# PLEN2_EdisonBoard.net
KiCad netlist of a schematic drawn in EAGLE
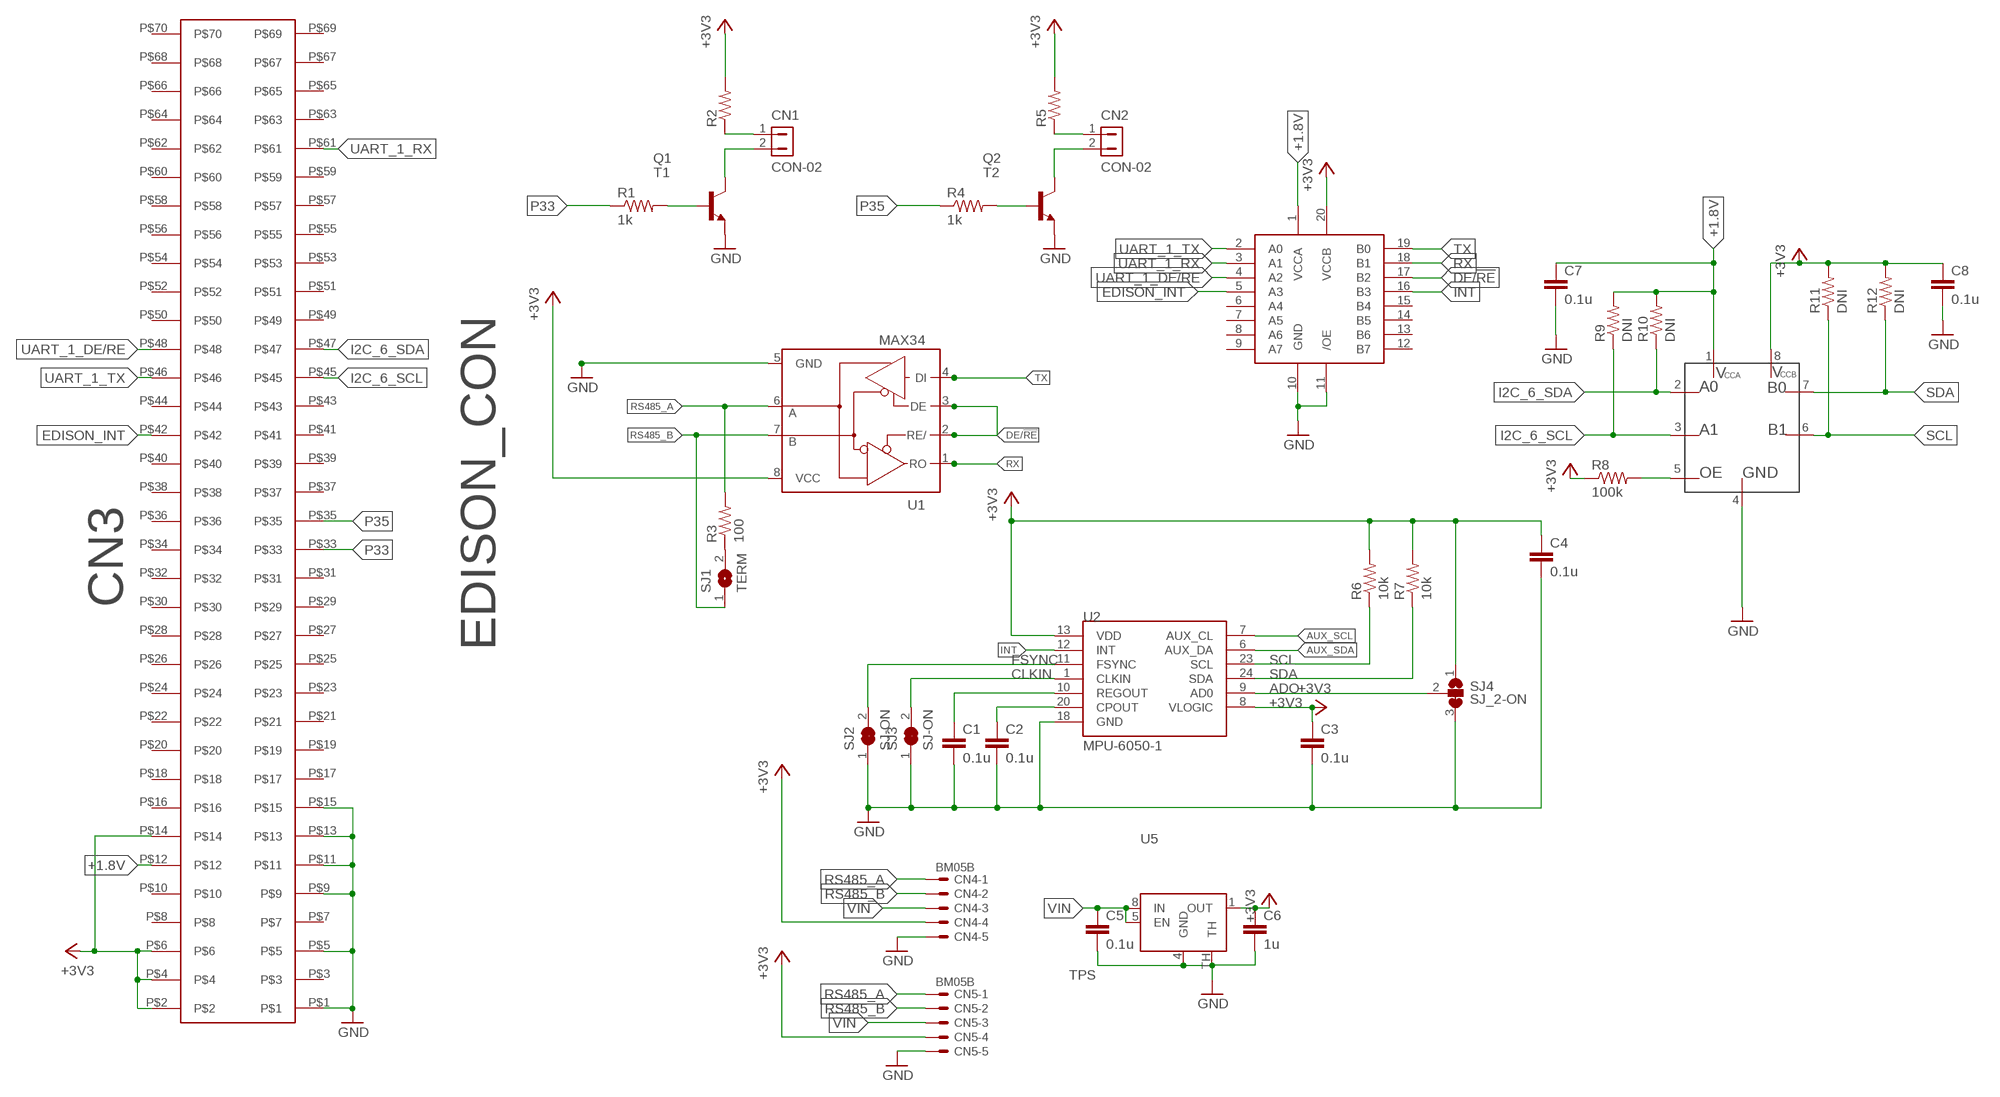
[diagram p0: schematic, sheet 1]

(export (version "E")
  (design (tool "Eeschema 10.0.6"))
  (components
    (comp (ref "C1")
      (value "0.1u")
      (footprint "eagle-import:C0603")
      (libsource (lib "eagle-import") (part "C-EUC0603"))
    )
    (comp (ref "C2")
      (value "0.1u")
      (footprint "eagle-import:C0603")
      (libsource (lib "eagle-import") (part "C-EUC0603"))
    )
    (comp (ref "C3")
      (value "0.1u")
      (footprint "eagle-import:C0603")
      (libsource (lib "eagle-import") (part "C-EUC0603"))
    )
    (comp (ref "C4")
      (value "0.1u")
      (footprint "eagle-import:C0603")
      (libsource (lib "eagle-import") (part "C-EUC0603"))
    )
    (comp (ref "C5")
      (value "0.1u")
      (footprint "eagle-import:C0603")
      (libsource (lib "eagle-import") (part "C-EUC0603"))
    )
    (comp (ref "C6")
      (value "1u")
      (footprint "eagle-import:C0603")
      (libsource (lib "eagle-import") (part "C-EUC0603"))
    )
    (comp (ref "C7")
      (value "0.1u")
      (footprint "eagle-import:C0603")
      (libsource (lib "eagle-import") (part "C-EUC0603"))
    )
    (comp (ref "C8")
      (value "0.1u")
      (footprint "eagle-import:C0603")
      (libsource (lib "eagle-import") (part "C-EUC0603"))
    )
    (comp (ref "CN1")
      (value "CON-02")
      (footprint "eagle-import:SIP-100-02")
      (libsource (lib "eagle-import") (part "CON-02"))
    )
    (comp (ref "CN2")
      (value "CON-02")
      (footprint "eagle-import:SIP-100-02")
      (libsource (lib "eagle-import") (part "CON-02"))
    )
    (comp (ref "CN3")
      (value "EDISON_CON")
      (footprint "eagle-import:EDISON_CON")
      (libsource (lib "eagle-import") (part "EDISON_CON"))
    )
    (comp (ref "CN4")
      (value "BM05B")
      (footprint "eagle-import:BM05B-SRSS-TB")
      (libsource (lib "eagle-import") (part "?M05B-SRSS-TBB"))
    )
    (comp (ref "CN5")
      (value "BM05B")
      (footprint "eagle-import:BM05B-SRSS-TB")
      (libsource (lib "eagle-import") (part "?M05B-SRSS-TBB"))
    )
    (comp (ref "Q1")
      (value "T1")
      (footprint "eagle-import:SOT23-BEC")
      (libsource (lib "eagle-import") (part "BC817SMD-40LT1"))
    )
    (comp (ref "Q2")
      (value "T2")
      (footprint "eagle-import:SOT23-BEC")
      (libsource (lib "eagle-import") (part "BC817SMD-40LT1"))
    )
    (comp (ref "R1")
      (value "1k")
      (footprint "eagle-import:R0603")
      (libsource (lib "eagle-import") (part "R-US_R0603"))
    )
    (comp (ref "R2")
      (value "R-US_R0603")
      (footprint "eagle-import:R0603")
      (libsource (lib "eagle-import") (part "R-US_R0603"))
    )
    (comp (ref "R3")
      (value "100")
      (footprint "eagle-import:R0603")
      (libsource (lib "eagle-import") (part "R-US_R0603"))
    )
    (comp (ref "R4")
      (value "1k")
      (footprint "eagle-import:R0603")
      (libsource (lib "eagle-import") (part "R-US_R0603"))
    )
    (comp (ref "R5")
      (value "R-US_R0603")
      (footprint "eagle-import:R0603")
      (libsource (lib "eagle-import") (part "R-US_R0603"))
    )
    (comp (ref "R6")
      (value "10k")
      (footprint "eagle-import:R0603")
      (libsource (lib "eagle-import") (part "R-US_R0603"))
    )
    (comp (ref "R7")
      (value "10k")
      (footprint "eagle-import:R0603")
      (libsource (lib "eagle-import") (part "R-US_R0603"))
    )
    (comp (ref "R8")
      (value "100k")
      (footprint "eagle-import:R0603")
      (libsource (lib "eagle-import") (part "R-US_R0603"))
    )
    (comp (ref "R9")
      (value "DNI")
      (footprint "eagle-import:R0603")
      (libsource (lib "eagle-import") (part "R-US_R0603"))
    )
    (comp (ref "R10")
      (value "DNI")
      (footprint "eagle-import:R0603")
      (libsource (lib "eagle-import") (part "R-US_R0603"))
    )
    (comp (ref "R11")
      (value "DNI")
      (footprint "eagle-import:R0603")
      (libsource (lib "eagle-import") (part "R-US_R0603"))
    )
    (comp (ref "R12")
      (value "DNI")
      (footprint "eagle-import:R0603")
      (libsource (lib "eagle-import") (part "R-US_R0603"))
    )
    (comp (ref "SJ1")
      (value "TERM")
      (footprint "eagle-import:SJ")
      (libsource (lib "eagle-import") (part "SJ"))
    )
    (comp (ref "SJ2")
      (value "SJ-ON")
      (footprint "eagle-import:SJ-ON")
      (libsource (lib "eagle-import") (part "SJ-ON"))
    )
    (comp (ref "SJ3")
      (value "SJ-ON")
      (footprint "eagle-import:SJ-ON")
      (libsource (lib "eagle-import") (part "SJ-ON"))
    )
    (comp (ref "SJ4")
      (value "SJ_2-ON")
      (footprint "eagle-import:SJ_2-ON")
      (libsource (lib "eagle-import") (part "SJ_2-ON"))
    )
    (comp (ref "U$2")
      (value "FXMA2102_MAC08A")
      (footprint "eagle-import:FXMA2102_MAC08A")
      (libsource (lib "eagle-import") (part "FXMA2102_MAC08A"))
    )
    (comp (ref "U1")
      (value "MAX34")
      (footprint "eagle-import:SO08SHORT")
      (libsource (lib "eagle-import") (part "MAX34SHORT"))
    )
    (comp (ref "U2")
      (value "MPU-6050-1")
      (footprint "eagle-import:QFN-24-4MM2")
      (libsource (lib "eagle-import") (part "MPU-6050-1"))
    )
    (comp (ref "U3")
      (value "FXMA108FXMA108")
      (footprint "eagle-import:FXMA108")
      (libsource (lib "eagle-import") (part "FXMA108FXMA108"))
    )
    (comp (ref "U5")
      (value "TPS")
      (footprint "eagle-import:S-PVSON-N8")
      (libsource (lib "eagle-import") (part "TPS73733"))
    )
  )
  (nets
    (net (code "1") (name "+1.8V") (class "Default")
      (node (ref "C7") (pin "1") (pinfunction "1_1") (pintype "passive"))
      (node (ref "CN3") (pin "P$12") (pinfunction "P$12_P$12") (pintype "bidirectional"))
      (node (ref "R10") (pin "2") (pinfunction "2_2") (pintype "passive"))
      (node (ref "R9") (pin "2") (pinfunction "2_2") (pintype "passive"))
      (node (ref "U$2") (pin "PIN1") (pinfunction "P1_PIN1") (pintype "bidirectional"))
      (node (ref "U3") (pin "1") (pinfunction "VCCA_1") (pintype "bidirectional"))
    )
    (net (code "2") (name "+3V3") (class "Default")
      (node (ref "C3") (pin "1") (pinfunction "1_1") (pintype "passive"))
      (node (ref "C4") (pin "1") (pinfunction "1_1") (pintype "passive"))
      (node (ref "C6") (pin "1") (pinfunction "1_1") (pintype "passive"))
      (node (ref "C8") (pin "1") (pinfunction "1_1") (pintype "passive"))
      (node (ref "CN3") (pin "P$14") (pinfunction "P$14_P$14") (pintype "bidirectional"))
      (node (ref "CN3") (pin "P$2") (pinfunction "P$2_P$2") (pintype "bidirectional"))
      (node (ref "CN3") (pin "P$4") (pinfunction "P$4_P$4") (pintype "bidirectional"))
      (node (ref "CN3") (pin "P$6") (pinfunction "P$6_P$6") (pintype "bidirectional"))
      (node (ref "CN4") (pin "4") (pinfunction "S_4") (pintype "passive"))
      (node (ref "CN5") (pin "4") (pinfunction "S_4") (pintype "passive"))
      (node (ref "R11") (pin "2") (pinfunction "2_2") (pintype "passive"))
      (node (ref "R12") (pin "2") (pinfunction "2_2") (pintype "passive"))
      (node (ref "R2") (pin "2") (pinfunction "2_2") (pintype "passive"))
      (node (ref "R5") (pin "2") (pinfunction "2_2") (pintype "passive"))
      (node (ref "R6") (pin "2") (pinfunction "2_2") (pintype "passive"))
      (node (ref "R7") (pin "2") (pinfunction "2_2") (pintype "passive"))
      (node (ref "R8") (pin "1") (pinfunction "1_1") (pintype "passive"))
      (node (ref "SJ4") (pin "1") (pinfunction "1_1") (pintype "passive"))
      (node (ref "U$2") (pin "PIN8") (pinfunction "P8_PIN8") (pintype "bidirectional"))
      (node (ref "U1") (pin "8") (pinfunction "VCC_8") (pintype "power_in"))
      (node (ref "U2") (pin "13") (pinfunction "VDD_13") (pintype "bidirectional"))
      (node (ref "U2") (pin "8") (pinfunction "VLOGIC_8") (pintype "bidirectional"))
      (node (ref "U3") (pin "20") (pinfunction "VCCB_20") (pintype "bidirectional"))
      (node (ref "U5") (pin "1") (pinfunction "OUT_1") (pintype "passive"))
    )
    (net (code "3") (name "/ADO") (class "Default")
      (node (ref "SJ4") (pin "2") (pinfunction "2_2") (pintype "passive"))
      (node (ref "U2") (pin "9") (pinfunction "AD0_9") (pintype "bidirectional"))
    )
    (net (code "4") (name "/CLKIN") (class "Default")
      (node (ref "SJ3") (pin "2") (pinfunction "2_2") (pintype "passive"))
      (node (ref "U2") (pin "1") (pinfunction "CLKIN_1") (pintype "bidirectional"))
    )
    (net (code "5") (name "/DE{slash}~{RE}") (class "Default")
      (node (ref "U1") (pin "2") (pinfunction "RE/_2") (pintype "input"))
      (node (ref "U1") (pin "3") (pinfunction "DE_3") (pintype "input"))
      (node (ref "U3") (pin "17") (pinfunction "B2_17") (pintype "bidirectional"))
    )
    (net (code "6") (name "/FSYNC") (class "Default")
      (node (ref "SJ2") (pin "2") (pinfunction "2_2") (pintype "passive"))
      (node (ref "U2") (pin "11") (pinfunction "FSYNC_11") (pintype "bidirectional"))
    )
    (net (code "7") (name "AUX_SCL") (class "Default")
      (node (ref "U2") (pin "7") (pinfunction "AUX_CL_7") (pintype "bidirectional"))
    )
    (net (code "8") (name "AUX_SDA") (class "Default")
      (node (ref "U2") (pin "6") (pinfunction "AUX_DA_6") (pintype "bidirectional"))
    )
    (net (code "9") (name "EDISON_INT") (class "Default")
      (node (ref "CN3") (pin "P$42") (pinfunction "P$42_P$42") (pintype "bidirectional"))
      (node (ref "U3") (pin "5") (pinfunction "A3_5") (pintype "bidirectional"))
    )
    (net (code "10") (name "GND") (class "Default")
      (node (ref "C1") (pin "2") (pinfunction "2_2") (pintype "passive"))
      (node (ref "C2") (pin "2") (pinfunction "2_2") (pintype "passive"))
      (node (ref "C3") (pin "2") (pinfunction "2_2") (pintype "passive"))
      (node (ref "C4") (pin "2") (pinfunction "2_2") (pintype "passive"))
      (node (ref "C5") (pin "2") (pinfunction "2_2") (pintype "passive"))
      (node (ref "C6") (pin "2") (pinfunction "2_2") (pintype "passive"))
      (node (ref "C7") (pin "2") (pinfunction "2_2") (pintype "passive"))
      (node (ref "C8") (pin "2") (pinfunction "2_2") (pintype "passive"))
      (node (ref "CN3") (pin "P$1") (pinfunction "P$1_P$1") (pintype "bidirectional"))
      (node (ref "CN3") (pin "P$11") (pinfunction "P$11_P$11") (pintype "bidirectional"))
      (node (ref "CN3") (pin "P$13") (pinfunction "P$13_P$13") (pintype "bidirectional"))
      (node (ref "CN3") (pin "P$15") (pinfunction "P$15_P$15") (pintype "bidirectional"))
      (node (ref "CN3") (pin "P$5") (pinfunction "P$5_P$5") (pintype "bidirectional"))
      (node (ref "CN3") (pin "P$9") (pinfunction "P$9_P$9") (pintype "bidirectional"))
      (node (ref "CN4") (pin "5") (pinfunction "S_5") (pintype "passive"))
      (node (ref "CN5") (pin "5") (pinfunction "S_5") (pintype "passive"))
      (node (ref "Q1") (pin "E") (pinfunction "E_E") (pintype "passive"))
      (node (ref "Q2") (pin "E") (pinfunction "E_E") (pintype "passive"))
      (node (ref "SJ2") (pin "1") (pinfunction "1_1") (pintype "passive"))
      (node (ref "SJ3") (pin "1") (pinfunction "1_1") (pintype "passive"))
      (node (ref "SJ4") (pin "3") (pinfunction "3_3") (pintype "passive"))
      (node (ref "U$2") (pin "PIN4") (pinfunction "P4_PIN4") (pintype "bidirectional"))
      (node (ref "U1") (pin "5") (pinfunction "GND_5") (pintype "power_in"))
      (node (ref "U2") (pin "18") (pinfunction "GND_18") (pintype "bidirectional"))
      (node (ref "U3") (pin "10") (pinfunction "GND_10") (pintype "bidirectional"))
      (node (ref "U3") (pin "11") (pinfunction "/OE_11") (pintype "bidirectional"))
      (node (ref "U5") (pin "4") (pinfunction "GND_4") (pintype "power_in"))
      (node (ref "U5") (pin "TH") (pinfunction "TH_TH") (pintype "power_in"))
    )
    (net (code "11") (name "I2C_6_SCL") (class "Default")
      (node (ref "CN3") (pin "P$45") (pinfunction "P$45_P$45") (pintype "bidirectional"))
      (node (ref "R9") (pin "1") (pinfunction "1_1") (pintype "passive"))
      (node (ref "U$2") (pin "PIN3") (pinfunction "P3_PIN3") (pintype "bidirectional"))
    )
    (net (code "12") (name "I2C_6_SDA") (class "Default")
      (node (ref "CN3") (pin "P$47") (pinfunction "P$47_P$47") (pintype "bidirectional"))
      (node (ref "R10") (pin "1") (pinfunction "1_1") (pintype "passive"))
      (node (ref "U$2") (pin "PIN2") (pinfunction "P2_PIN2") (pintype "bidirectional"))
    )
    (net (code "13") (name "INT") (class "Default")
      (node (ref "U2") (pin "12") (pinfunction "INT_12") (pintype "bidirectional"))
      (node (ref "U3") (pin "16") (pinfunction "B3_16") (pintype "bidirectional"))
    )
    (net (code "14") (name "Net-(CN1-Pad1)") (class "Default")
      (node (ref "CN1") (pin "1") (pinfunction "1_1") (pintype "passive"))
      (node (ref "R2") (pin "1") (pinfunction "1_1") (pintype "passive"))
    )
    (net (code "15") (name "Net-(CN1-Pad2)") (class "Default")
      (node (ref "CN1") (pin "2") (pinfunction "2_2") (pintype "passive"))
      (node (ref "Q1") (pin "C") (pinfunction "C_C") (pintype "passive"))
    )
    (net (code "16") (name "Net-(CN2-Pad1)") (class "Default")
      (node (ref "CN2") (pin "1") (pinfunction "1_1") (pintype "passive"))
      (node (ref "R5") (pin "1") (pinfunction "1_1") (pintype "passive"))
    )
    (net (code "17") (name "Net-(CN2-Pad2)") (class "Default")
      (node (ref "CN2") (pin "2") (pinfunction "2_2") (pintype "passive"))
      (node (ref "Q2") (pin "C") (pinfunction "C_C") (pintype "passive"))
    )
    (net (code "18") (name "Net-(Q1-PadB)") (class "Default")
      (node (ref "Q1") (pin "B") (pinfunction "B_B") (pintype "passive"))
      (node (ref "R1") (pin "2") (pinfunction "2_2") (pintype "passive"))
    )
    (net (code "19") (name "Net-(Q2-PadB)") (class "Default")
      (node (ref "Q2") (pin "B") (pinfunction "B_B") (pintype "passive"))
      (node (ref "R4") (pin "2") (pinfunction "2_2") (pintype "passive"))
    )
    (net (code "20") (name "Net-(R3-Pad1)") (class "Default")
      (node (ref "R3") (pin "1") (pinfunction "1_1") (pintype "passive"))
      (node (ref "SJ1") (pin "2") (pinfunction "2_2") (pintype "passive"))
    )
    (net (code "21") (name "Net-(U$2-P5)") (class "Default")
      (node (ref "R8") (pin "2") (pinfunction "2_2") (pintype "passive"))
      (node (ref "U$2") (pin "PIN5") (pinfunction "P5_PIN5") (pintype "bidirectional"))
    )
    (net (code "22") (name "Net-(U2-CPOUT)") (class "Default")
      (node (ref "C2") (pin "1") (pinfunction "1_1") (pintype "passive"))
      (node (ref "U2") (pin "20") (pinfunction "CPOUT_20") (pintype "bidirectional"))
    )
    (net (code "23") (name "Net-(U2-REGOUT)") (class "Default")
      (node (ref "C1") (pin "1") (pinfunction "1_1") (pintype "passive"))
      (node (ref "U2") (pin "10") (pinfunction "REGOUT_10") (pintype "bidirectional"))
    )
    (net (code "24") (name "P33") (class "Default")
      (node (ref "CN3") (pin "P$33") (pinfunction "P$33_P$33") (pintype "bidirectional"))
      (node (ref "R1") (pin "1") (pinfunction "1_1") (pintype "passive"))
    )
    (net (code "25") (name "P35") (class "Default")
      (node (ref "CN3") (pin "P$35") (pinfunction "P$35_P$35") (pintype "bidirectional"))
      (node (ref "R4") (pin "1") (pinfunction "1_1") (pintype "passive"))
    )
    (net (code "26") (name "RS485_A") (class "Default")
      (node (ref "CN4") (pin "1") (pinfunction "S_1") (pintype "passive"))
      (node (ref "CN5") (pin "1") (pinfunction "S_1") (pintype "passive"))
      (node (ref "R3") (pin "2") (pinfunction "2_2") (pintype "passive"))
      (node (ref "U1") (pin "6") (pinfunction "A_6") (pintype "passive"))
    )
    (net (code "27") (name "RS485_B") (class "Default")
      (node (ref "CN4") (pin "2") (pinfunction "S_2") (pintype "passive"))
      (node (ref "CN5") (pin "2") (pinfunction "S_2") (pintype "passive"))
      (node (ref "SJ1") (pin "1") (pinfunction "1_1") (pintype "passive"))
      (node (ref "U1") (pin "7") (pinfunction "B_7") (pintype "passive"))
    )
    (net (code "28") (name "RX") (class "Default")
      (node (ref "U1") (pin "1") (pinfunction "RO_1") (pintype "output"))
      (node (ref "U3") (pin "18") (pinfunction "B1_18") (pintype "bidirectional"))
    )
    (net (code "29") (name "SCL") (class "Default")
      (node (ref "R11") (pin "1") (pinfunction "1_1") (pintype "passive"))
      (node (ref "R6") (pin "1") (pinfunction "1_1") (pintype "passive"))
      (node (ref "U$2") (pin "PIN6") (pinfunction "P6_PIN6") (pintype "bidirectional"))
      (node (ref "U2") (pin "23") (pinfunction "SCL_23") (pintype "bidirectional"))
    )
    (net (code "30") (name "SDA") (class "Default")
      (node (ref "R12") (pin "1") (pinfunction "1_1") (pintype "passive"))
      (node (ref "R7") (pin "1") (pinfunction "1_1") (pintype "passive"))
      (node (ref "U$2") (pin "PIN7") (pinfunction "P7_PIN7") (pintype "bidirectional"))
      (node (ref "U2") (pin "24") (pinfunction "SDA_24") (pintype "bidirectional"))
    )
    (net (code "31") (name "TX") (class "Default")
      (node (ref "U1") (pin "4") (pinfunction "DI_4") (pintype "input"))
      (node (ref "U3") (pin "19") (pinfunction "B0_19") (pintype "bidirectional"))
    )
    (net (code "32") (name "UART_1_DE{slash}RE") (class "Default")
      (node (ref "CN3") (pin "P$48") (pinfunction "P$48_P$48") (pintype "bidirectional"))
      (node (ref "U3") (pin "4") (pinfunction "A2_4") (pintype "bidirectional"))
    )
    (net (code "33") (name "UART_1_RX") (class "Default")
      (node (ref "CN3") (pin "P$61") (pinfunction "P$61_P$61") (pintype "bidirectional"))
      (node (ref "U3") (pin "3") (pinfunction "A1_3") (pintype "bidirectional"))
    )
    (net (code "34") (name "UART_1_TX") (class "Default")
      (node (ref "CN3") (pin "P$46") (pinfunction "P$46_P$46") (pintype "bidirectional"))
      (node (ref "U3") (pin "2") (pinfunction "A0_2") (pintype "bidirectional"))
    )
    (net (code "35") (name "VIN") (class "Default")
      (node (ref "C5") (pin "1") (pinfunction "1_1") (pintype "passive"))
      (node (ref "CN4") (pin "3") (pinfunction "S_3") (pintype "passive"))
      (node (ref "CN5") (pin "3") (pinfunction "S_3") (pintype "passive"))
      (node (ref "U5") (pin "5") (pinfunction "EN_5") (pintype "input"))
      (node (ref "U5") (pin "8") (pinfunction "IN_8") (pintype "input"))
    )
    (net (code "36") (name "unconnected-(CN3-PadP$3)") (class "Default")
      (node (ref "CN3") (pin "P$3") (pinfunction "P$3_P$3") (pintype "bidirectional"))
    )
    (net (code "37") (name "unconnected-(CN3-PadP$7)") (class "Default")
      (node (ref "CN3") (pin "P$7") (pinfunction "P$7_P$7") (pintype "bidirectional"))
    )
    (net (code "38") (name "unconnected-(CN3-PadP$8)") (class "Default")
      (node (ref "CN3") (pin "P$8") (pinfunction "P$8_P$8") (pintype "bidirectional"))
    )
    (net (code "39") (name "unconnected-(CN3-PadP$10)") (class "Default")
      (node (ref "CN3") (pin "P$10") (pinfunction "P$10_P$10") (pintype "bidirectional"))
    )
    (net (code "40") (name "unconnected-(CN3-PadP$16)") (class "Default")
      (node (ref "CN3") (pin "P$16") (pinfunction "P$16_P$16") (pintype "bidirectional"))
    )
    (net (code "41") (name "unconnected-(CN3-PadP$17)") (class "Default")
      (node (ref "CN3") (pin "P$17") (pinfunction "P$17_P$17") (pintype "bidirectional"))
    )
    (net (code "42") (name "unconnected-(CN3-PadP$18)") (class "Default")
      (node (ref "CN3") (pin "P$18") (pinfunction "P$18_P$18") (pintype "bidirectional"))
    )
    (net (code "43") (name "unconnected-(CN3-PadP$19)") (class "Default")
      (node (ref "CN3") (pin "P$19") (pinfunction "P$19_P$19") (pintype "bidirectional"))
    )
    (net (code "44") (name "unconnected-(CN3-PadP$20)") (class "Default")
      (node (ref "CN3") (pin "P$20") (pinfunction "P$20_P$20") (pintype "bidirectional"))
    )
    (net (code "45") (name "unconnected-(CN3-PadP$21)") (class "Default")
      (node (ref "CN3") (pin "P$21") (pinfunction "P$21_P$21") (pintype "bidirectional"))
    )
    (net (code "46") (name "unconnected-(CN3-PadP$22)") (class "Default")
      (node (ref "CN3") (pin "P$22") (pinfunction "P$22_P$22") (pintype "bidirectional"))
    )
    (net (code "47") (name "unconnected-(CN3-PadP$23)") (class "Default")
      (node (ref "CN3") (pin "P$23") (pinfunction "P$23_P$23") (pintype "bidirectional"))
    )
    (net (code "48") (name "unconnected-(CN3-PadP$24)") (class "Default")
      (node (ref "CN3") (pin "P$24") (pinfunction "P$24_P$24") (pintype "bidirectional"))
    )
    (net (code "49") (name "unconnected-(CN3-PadP$25)") (class "Default")
      (node (ref "CN3") (pin "P$25") (pinfunction "P$25_P$25") (pintype "bidirectional"))
    )
    (net (code "50") (name "unconnected-(CN3-PadP$26)") (class "Default")
      (node (ref "CN3") (pin "P$26") (pinfunction "P$26_P$26") (pintype "bidirectional"))
    )
    (net (code "51") (name "unconnected-(CN3-PadP$27)") (class "Default")
      (node (ref "CN3") (pin "P$27") (pinfunction "P$27_P$27") (pintype "bidirectional"))
    )
    (net (code "52") (name "unconnected-(CN3-PadP$28)") (class "Default")
      (node (ref "CN3") (pin "P$28") (pinfunction "P$28_P$28") (pintype "bidirectional"))
    )
    (net (code "53") (name "unconnected-(CN3-PadP$29)") (class "Default")
      (node (ref "CN3") (pin "P$29") (pinfunction "P$29_P$29") (pintype "bidirectional"))
    )
    (net (code "54") (name "unconnected-(CN3-PadP$30)") (class "Default")
      (node (ref "CN3") (pin "P$30") (pinfunction "P$30_P$30") (pintype "bidirectional"))
    )
    (net (code "55") (name "unconnected-(CN3-PadP$31)") (class "Default")
      (node (ref "CN3") (pin "P$31") (pinfunction "P$31_P$31") (pintype "bidirectional"))
    )
    (net (code "56") (name "unconnected-(CN3-PadP$32)") (class "Default")
      (node (ref "CN3") (pin "P$32") (pinfunction "P$32_P$32") (pintype "bidirectional"))
    )
    (net (code "57") (name "unconnected-(CN3-PadP$34)") (class "Default")
      (node (ref "CN3") (pin "P$34") (pinfunction "P$34_P$34") (pintype "bidirectional"))
    )
    (net (code "58") (name "unconnected-(CN3-PadP$36)") (class "Default")
      (node (ref "CN3") (pin "P$36") (pinfunction "P$36_P$36") (pintype "bidirectional"))
    )
    (net (code "59") (name "unconnected-(CN3-PadP$37)") (class "Default")
      (node (ref "CN3") (pin "P$37") (pinfunction "P$37_P$37") (pintype "bidirectional"))
    )
    (net (code "60") (name "unconnected-(CN3-PadP$38)") (class "Default")
      (node (ref "CN3") (pin "P$38") (pinfunction "P$38_P$38") (pintype "bidirectional"))
    )
    (net (code "61") (name "unconnected-(CN3-PadP$39)") (class "Default")
      (node (ref "CN3") (pin "P$39") (pinfunction "P$39_P$39") (pintype "bidirectional"))
    )
    (net (code "62") (name "unconnected-(CN3-PadP$40)") (class "Default")
      (node (ref "CN3") (pin "P$40") (pinfunction "P$40_P$40") (pintype "bidirectional"))
    )
    (net (code "63") (name "unconnected-(CN3-PadP$41)") (class "Default")
      (node (ref "CN3") (pin "P$41") (pinfunction "P$41_P$41") (pintype "bidirectional"))
    )
    (net (code "64") (name "unconnected-(CN3-PadP$43)") (class "Default")
      (node (ref "CN3") (pin "P$43") (pinfunction "P$43_P$43") (pintype "bidirectional"))
    )
    (net (code "65") (name "unconnected-(CN3-PadP$44)") (class "Default")
      (node (ref "CN3") (pin "P$44") (pinfunction "P$44_P$44") (pintype "bidirectional"))
    )
    (net (code "66") (name "unconnected-(CN3-PadP$49)") (class "Default")
      (node (ref "CN3") (pin "P$49") (pinfunction "P$49_P$49") (pintype "bidirectional"))
    )
    (net (code "67") (name "unconnected-(CN3-PadP$50)") (class "Default")
      (node (ref "CN3") (pin "P$50") (pinfunction "P$50_P$50") (pintype "bidirectional"))
    )
    (net (code "68") (name "unconnected-(CN3-PadP$51)") (class "Default")
      (node (ref "CN3") (pin "P$51") (pinfunction "P$51_P$51") (pintype "bidirectional"))
    )
    (net (code "69") (name "unconnected-(CN3-PadP$52)") (class "Default")
      (node (ref "CN3") (pin "P$52") (pinfunction "P$52_P$52") (pintype "bidirectional"))
    )
    (net (code "70") (name "unconnected-(CN3-PadP$53)") (class "Default")
      (node (ref "CN3") (pin "P$53") (pinfunction "P$53_P$53") (pintype "bidirectional"))
    )
    (net (code "71") (name "unconnected-(CN3-PadP$54)") (class "Default")
      (node (ref "CN3") (pin "P$54") (pinfunction "P$54_P$54") (pintype "bidirectional"))
    )
    (net (code "72") (name "unconnected-(CN3-PadP$55)") (class "Default")
      (node (ref "CN3") (pin "P$55") (pinfunction "P$55_P$55") (pintype "bidirectional"))
    )
    (net (code "73") (name "unconnected-(CN3-PadP$56)") (class "Default")
      (node (ref "CN3") (pin "P$56") (pinfunction "P$56_P$56") (pintype "bidirectional"))
    )
    (net (code "74") (name "unconnected-(CN3-PadP$57)") (class "Default")
      (node (ref "CN3") (pin "P$57") (pinfunction "P$57_P$57") (pintype "bidirectional"))
    )
    (net (code "75") (name "unconnected-(CN3-PadP$58)") (class "Default")
      (node (ref "CN3") (pin "P$58") (pinfunction "P$58_P$58") (pintype "bidirectional"))
    )
    (net (code "76") (name "unconnected-(CN3-PadP$59)") (class "Default")
      (node (ref "CN3") (pin "P$59") (pinfunction "P$59_P$59") (pintype "bidirectional"))
    )
    (net (code "77") (name "unconnected-(CN3-PadP$60)") (class "Default")
      (node (ref "CN3") (pin "P$60") (pinfunction "P$60_P$60") (pintype "bidirectional"))
    )
    (net (code "78") (name "unconnected-(CN3-PadP$62)") (class "Default")
      (node (ref "CN3") (pin "P$62") (pinfunction "P$62_P$62") (pintype "bidirectional"))
    )
    (net (code "79") (name "unconnected-(CN3-PadP$63)") (class "Default")
      (node (ref "CN3") (pin "P$63") (pinfunction "P$63_P$63") (pintype "bidirectional"))
    )
    (net (code "80") (name "unconnected-(CN3-PadP$64)") (class "Default")
      (node (ref "CN3") (pin "P$64") (pinfunction "P$64_P$64") (pintype "bidirectional"))
    )
    (net (code "81") (name "unconnected-(CN3-PadP$65)") (class "Default")
      (node (ref "CN3") (pin "P$65") (pinfunction "P$65_P$65") (pintype "bidirectional"))
    )
    (net (code "82") (name "unconnected-(CN3-PadP$66)") (class "Default")
      (node (ref "CN3") (pin "P$66") (pinfunction "P$66_P$66") (pintype "bidirectional"))
    )
    (net (code "83") (name "unconnected-(CN3-PadP$67)") (class "Default")
      (node (ref "CN3") (pin "P$67") (pinfunction "P$67_P$67") (pintype "bidirectional"))
    )
    (net (code "84") (name "unconnected-(CN3-PadP$68)") (class "Default")
      (node (ref "CN3") (pin "P$68") (pinfunction "P$68_P$68") (pintype "bidirectional"))
    )
    (net (code "85") (name "unconnected-(CN3-PadP$69)") (class "Default")
      (node (ref "CN3") (pin "P$69") (pinfunction "P$69_P$69") (pintype "bidirectional"))
    )
    (net (code "86") (name "unconnected-(CN3-PadP$70)") (class "Default")
      (node (ref "CN3") (pin "P$70") (pinfunction "P$70_P$70") (pintype "bidirectional"))
    )
    (net (code "87") (name "unconnected-(U3-A4-Pad6)") (class "Default")
      (node (ref "U3") (pin "6") (pinfunction "A4_6") (pintype "bidirectional"))
    )
    (net (code "88") (name "unconnected-(U3-A5-Pad7)") (class "Default")
      (node (ref "U3") (pin "7") (pinfunction "A5_7") (pintype "bidirectional"))
    )
    (net (code "89") (name "unconnected-(U3-A6-Pad8)") (class "Default")
      (node (ref "U3") (pin "8") (pinfunction "A6_8") (pintype "bidirectional"))
    )
    (net (code "90") (name "unconnected-(U3-A7-Pad9)") (class "Default")
      (node (ref "U3") (pin "9") (pinfunction "A7_9") (pintype "bidirectional"))
    )
    (net (code "91") (name "unconnected-(U3-B4-Pad15)") (class "Default")
      (node (ref "U3") (pin "15") (pinfunction "B4_15") (pintype "bidirectional"))
    )
    (net (code "92") (name "unconnected-(U3-B5-Pad14)") (class "Default")
      (node (ref "U3") (pin "14") (pinfunction "B5_14") (pintype "bidirectional"))
    )
    (net (code "93") (name "unconnected-(U3-B6-Pad13)") (class "Default")
      (node (ref "U3") (pin "13") (pinfunction "B6_13") (pintype "bidirectional"))
    )
    (net (code "94") (name "unconnected-(U3-B7-Pad12)") (class "Default")
      (node (ref "U3") (pin "12") (pinfunction "B7_12") (pintype "bidirectional"))
    )
  )
)
